# I2CShifter.net
KiCad netlist of a schematic drawn in Altium Designer
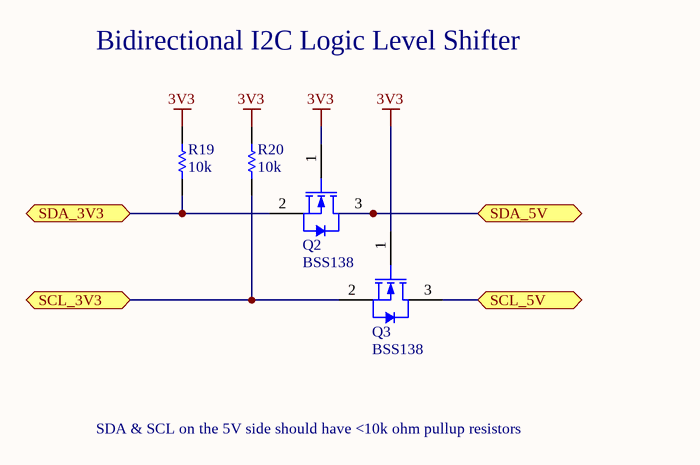
[diagram p0: I2CShifter.SchDoc]

(export (version "E")
  (design (tool "Eeschema 10.0.6"))
  (components
    (comp (ref "Q2")
      (value "BSS138")
      (footprint "FAIR-SOT23-3_V")
      (fields (field (name "TOLERANCE") "30ppm"))
      (libsource (lib "Altium Content Vault") (part "NEMOS-GSD-3"))
    )
    (comp (ref "Q3")
      (value "BSS138")
      (footprint "FAIR-SOT23-3_V")
      (fields (field (name "TOLERANCE") "30ppm"))
      (libsource (lib "Altium Content Vault") (part "NEMOS-GSD-3"))
    )
    (comp (ref "R19")
      (value "10k")
      (footprint "RESC0603(1608)_L")
      (description "10K 0.1W 5% 0603 (1608 Metric)  SMD")
      (fields (field (name "TOLERANCE") "5 %") (field (name "POWER") "0.1 W"))
      (libsource (lib "Altium Content Vault") (part "RES"))
    )
    (comp (ref "R20")
      (value "10k")
      (footprint "RESC0603(1608)_L")
      (description "10K 0.1W 5% 0603 (1608 Metric)  SMD")
      (fields (field (name "TOLERANCE") "5 %") (field (name "POWER") "0.1 W"))
      (libsource (lib "Altium Content Vault") (part "RES"))
    )
  )
  (nets
    (net (code "1") (name "/SCL_3V3") (class "Default")
      (node (ref "Q3") (pin "2") (pinfunction "S_2") (pintype "passive"))
      (node (ref "R20") (pin "1") (pinfunction "1_1") (pintype "passive"))
    )
    (net (code "2") (name "/SCL_5V") (class "Default")
      (node (ref "Q3") (pin "3") (pinfunction "D_3") (pintype "passive"))
    )
    (net (code "3") (name "/SDA_3V3") (class "Default")
      (node (ref "Q2") (pin "2") (pinfunction "S_2") (pintype "passive"))
      (node (ref "R19") (pin "1") (pinfunction "1_1") (pintype "passive"))
    )
    (net (code "4") (name "/SDA_5V") (class "Default")
      (node (ref "Q2") (pin "3") (pinfunction "D_3") (pintype "passive"))
    )
    (net (code "5") (name "3V3") (class "Default")
      (node (ref "Q2") (pin "1") (pinfunction "G_1") (pintype "passive"))
      (node (ref "Q3") (pin "1") (pinfunction "G_1") (pintype "passive"))
      (node (ref "R19") (pin "2") (pinfunction "2_2") (pintype "passive"))
      (node (ref "R20") (pin "2") (pinfunction "2_2") (pintype "passive"))
    )
  )
)
